# NPKC_alt_PCB.net
KiCad netlist of a schematic drawn in EAGLE
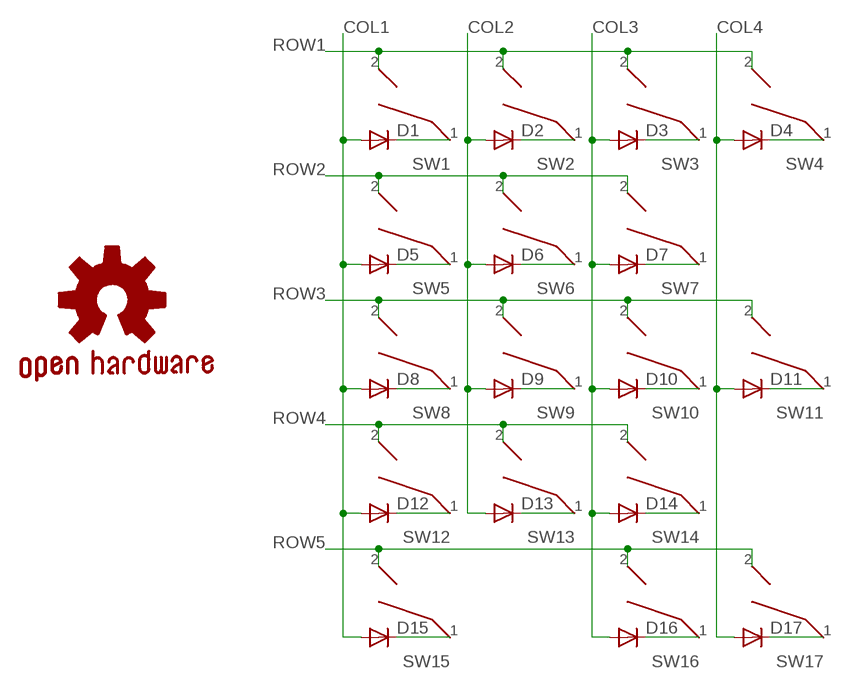
[diagram p0: schematic, sheet 1]
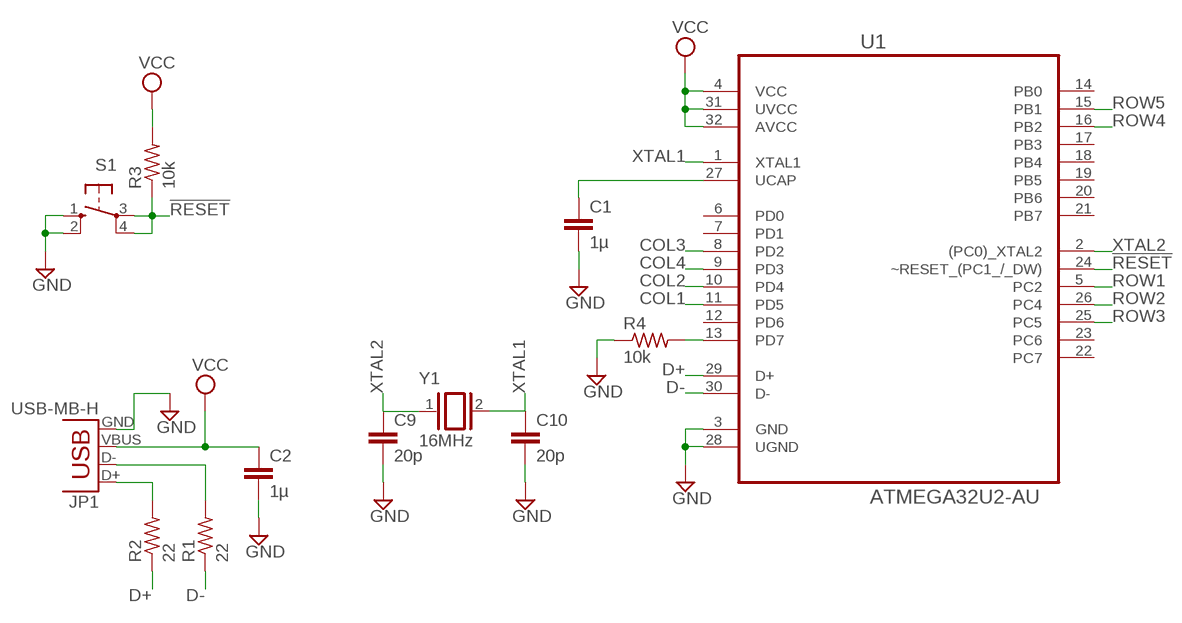
[diagram p1: schematic, sheet 2]

(export (version "E")
  (design (tool "Eeschema 10.0.6"))
  (components
    (comp (ref "D1")
      (value "CGRM4001-G")
      (footprint "eagle-import:SOD-123_MINI-SMA")
      (libsource (lib "eagle-import") (part "CGRM400-G1"))
    )
    (comp (ref "D2")
      (value "CGRM4001-G")
      (footprint "eagle-import:SOD-123_MINI-SMA")
      (libsource (lib "eagle-import") (part "CGRM400-G1"))
    )
    (comp (ref "D3")
      (value "CGRM4001-G")
      (footprint "eagle-import:SOD-123_MINI-SMA")
      (libsource (lib "eagle-import") (part "CGRM400-G1"))
    )
    (comp (ref "D4")
      (value "CGRM4001-G")
      (footprint "eagle-import:SOD-123_MINI-SMA")
      (libsource (lib "eagle-import") (part "CGRM400-G1"))
    )
    (comp (ref "D5")
      (value "CGRM4001-G")
      (footprint "eagle-import:SOD-123_MINI-SMA")
      (libsource (lib "eagle-import") (part "CGRM400-G1"))
    )
    (comp (ref "D6")
      (value "CGRM4001-G")
      (footprint "eagle-import:SOD-123_MINI-SMA")
      (libsource (lib "eagle-import") (part "CGRM400-G1"))
    )
    (comp (ref "D7")
      (value "CGRM4001-G")
      (footprint "eagle-import:SOD-123_MINI-SMA")
      (libsource (lib "eagle-import") (part "CGRM400-G1"))
    )
    (comp (ref "D8")
      (value "CGRM4001-G")
      (footprint "eagle-import:SOD-123_MINI-SMA")
      (libsource (lib "eagle-import") (part "CGRM400-G1"))
    )
    (comp (ref "D9")
      (value "CGRM4001-G")
      (footprint "eagle-import:SOD-123_MINI-SMA")
      (libsource (lib "eagle-import") (part "CGRM400-G1"))
    )
    (comp (ref "D10")
      (value "CGRM4001-G")
      (footprint "eagle-import:SOD-123_MINI-SMA")
      (libsource (lib "eagle-import") (part "CGRM400-G1"))
    )
    (comp (ref "D11")
      (value "CGRM4001-G")
      (footprint "eagle-import:SOD-123_MINI-SMA")
      (libsource (lib "eagle-import") (part "CGRM400-G1"))
    )
    (comp (ref "D12")
      (value "CGRM4001-G")
      (footprint "eagle-import:SOD-123_MINI-SMA")
      (libsource (lib "eagle-import") (part "CGRM400-G1"))
    )
    (comp (ref "D13")
      (value "CGRM4001-G")
      (footprint "eagle-import:SOD-123_MINI-SMA")
      (libsource (lib "eagle-import") (part "CGRM400-G1"))
    )
    (comp (ref "D14")
      (value "CGRM4001-G")
      (footprint "eagle-import:SOD-123_MINI-SMA")
      (libsource (lib "eagle-import") (part "CGRM400-G1"))
    )
    (comp (ref "D15")
      (value "CGRM4001-G")
      (footprint "eagle-import:SOD-123_MINI-SMA")
      (libsource (lib "eagle-import") (part "CGRM400-G1"))
    )
    (comp (ref "D16")
      (value "CGRM4001-G")
      (footprint "eagle-import:SOD-123_MINI-SMA")
      (libsource (lib "eagle-import") (part "CGRM400-G1"))
    )
    (comp (ref "D17")
      (value "CGRM4001-G")
      (footprint "eagle-import:SOD-123_MINI-SMA")
      (libsource (lib "eagle-import") (part "CGRM400-G1"))
    )
    (comp (ref "GOLD_ORB_SM1")
      (value "OSHWLOGO_GOLD_ORB_SM")
      (footprint "eagle-import:OSHW2")
      (libsource (lib "eagle-import") (part "OSHWLOGO_GOLD_ORB_SM"))
    )
    (comp (ref "SW1")
      (value "Num_Lock")
      (footprint "eagle-import:MX1A-XXNW")
      (libsource (lib "eagle-import") (part "CHERRY_MX_WITH_FIXING_PINS"))
    )
    (comp (ref "SW2")
      (value "NP_/")
      (footprint "eagle-import:MX1A-XXNW")
      (libsource (lib "eagle-import") (part "CHERRY_MX_WITH_FIXING_PINS"))
    )
    (comp (ref "SW3")
      (value "NP_*")
      (footprint "eagle-import:MX1A-XXNW")
      (libsource (lib "eagle-import") (part "CHERRY_MX_WITH_FIXING_PINS"))
    )
    (comp (ref "SW4")
      (value "NP_-")
      (footprint "eagle-import:MX1A-XXNW")
      (libsource (lib "eagle-import") (part "CHERRY_MX_WITH_FIXING_PINS"))
    )
    (comp (ref "SW5")
      (value "NP_7")
      (footprint "eagle-import:MX1A-XXNW")
      (libsource (lib "eagle-import") (part "CHERRY_MX_WITH_FIXING_PINS"))
    )
    (comp (ref "SW6")
      (value "NP_8")
      (footprint "eagle-import:MX1A-XXNW")
      (libsource (lib "eagle-import") (part "CHERRY_MX_WITH_FIXING_PINS"))
    )
    (comp (ref "SW7")
      (value "NP_9")
      (footprint "eagle-import:MX1A-XXNW")
      (libsource (lib "eagle-import") (part "CHERRY_MX_WITH_FIXING_PINS"))
    )
    (comp (ref "SW8")
      (value "NP_4")
      (footprint "eagle-import:MX1A-XXNW")
      (libsource (lib "eagle-import") (part "CHERRY_MX_WITH_FIXING_PINS"))
    )
    (comp (ref "SW9")
      (value "NP_5")
      (footprint "eagle-import:MX1A-XXNW")
      (libsource (lib "eagle-import") (part "CHERRY_MX_WITH_FIXING_PINS"))
    )
    (comp (ref "SW10")
      (value "NP_6")
      (footprint "eagle-import:MX1A-XXNW")
      (libsource (lib "eagle-import") (part "CHERRY_MX_WITH_FIXING_PINS"))
    )
    (comp (ref "SW11")
      (value "NP_+")
      (footprint "eagle-import:MX1A-XXNW")
      (libsource (lib "eagle-import") (part "CHERRY_MX_WITH_FIXING_PINS"))
    )
    (comp (ref "SW12")
      (value "NP_1")
      (footprint "eagle-import:MX1A-XXNW")
      (libsource (lib "eagle-import") (part "CHERRY_MX_WITH_FIXING_PINS"))
    )
    (comp (ref "SW13")
      (value "NP_2")
      (footprint "eagle-import:MX1A-XXNW")
      (libsource (lib "eagle-import") (part "CHERRY_MX_WITH_FIXING_PINS"))
    )
    (comp (ref "SW14")
      (value "NP_3")
      (footprint "eagle-import:MX1A-XXNW")
      (libsource (lib "eagle-import") (part "CHERRY_MX_WITH_FIXING_PINS"))
    )
    (comp (ref "SW15")
      (value "NP_0")
      (footprint "eagle-import:MX1A-XXNW")
      (libsource (lib "eagle-import") (part "CHERRY_MX_WITH_FIXING_PINS"))
    )
    (comp (ref "SW16")
      (value "NP_.")
      (footprint "eagle-import:MX1A-XXNW")
      (libsource (lib "eagle-import") (part "CHERRY_MX_WITH_FIXING_PINS"))
    )
    (comp (ref "SW17")
      (value "NP_Enter")
      (footprint "eagle-import:MX1A-XXNW")
      (libsource (lib "eagle-import") (part "CHERRY_MX_WITH_FIXING_PINS"))
    )
    (comp (ref "C1")
      (value "1µ")
      (footprint "eagle-import:C0805K")
      (libsource (lib "eagle-import") (part "C-EUC0805K"))
    )
    (comp (ref "C2")
      (value "1µ")
      (footprint "eagle-import:C0805")
      (libsource (lib "eagle-import") (part "C-EUC0805"))
    )
    (comp (ref "C9")
      (value "20p")
      (footprint "eagle-import:C0805K")
      (libsource (lib "eagle-import") (part "C-EUC0805K"))
    )
    (comp (ref "C10")
      (value "20p")
      (footprint "eagle-import:C0805K")
      (libsource (lib "eagle-import") (part "C-EUC0805K"))
    )
    (comp (ref "JP1")
      (value "USB-MB-H")
      (footprint "eagle-import:USB-MB-H")
      (libsource (lib "eagle-import") (part "USB-MB-H"))
    )
    (comp (ref "R1")
      (value "22")
      (footprint "eagle-import:R0805")
      (libsource (lib "eagle-import") (part "R-US_R0805"))
    )
    (comp (ref "R2")
      (value "22")
      (footprint "eagle-import:R0805")
      (libsource (lib "eagle-import") (part "R-US_R0805"))
    )
    (comp (ref "R3")
      (value "10k")
      (footprint "eagle-import:R0805")
      (libsource (lib "eagle-import") (part "R-US_R0805"))
    )
    (comp (ref "R4")
      (value "10k")
      (footprint "eagle-import:R0805")
      (libsource (lib "eagle-import") (part "R-US_R0805"))
    )
    (comp (ref "S1")
      (value "10-XX")
      (footprint "eagle-import:B3F-10XX")
      (fields (field (name "MPN") "B3F-1000"))
      (libsource (lib "eagle-import") (part "10-XX"))
    )
    (comp (ref "U1")
      (value "ATMEGA32U2-AU")
      (footprint "eagle-import:QFP80P900X900X120-32N")
      (libsource (lib "eagle-import") (part "ATMEGA32U2-AU"))
    )
    (comp (ref "Y1")
      (value "16MHz")
      (footprint "eagle-import:QS")
      (libsource (lib "eagle-import") (part "XTAL/S"))
    )
  )
  (nets
    (net (code "1") (name "COL1") (class "Default")
      (node (ref "D1") (pin "A") (pinfunction "A_A") (pintype "passive"))
      (node (ref "D12") (pin "A") (pinfunction "A_A") (pintype "passive"))
      (node (ref "D15") (pin "A") (pinfunction "A_A") (pintype "passive"))
      (node (ref "D5") (pin "A") (pinfunction "A_A") (pintype "passive"))
      (node (ref "D8") (pin "A") (pinfunction "A_A") (pintype "passive"))
      (node (ref "U1") (pin "11") (pinfunction "PD5_11") (pintype "bidirectional"))
    )
    (net (code "2") (name "COL2") (class "Default")
      (node (ref "D13") (pin "A") (pinfunction "A_A") (pintype "passive"))
      (node (ref "D2") (pin "A") (pinfunction "A_A") (pintype "passive"))
      (node (ref "D6") (pin "A") (pinfunction "A_A") (pintype "passive"))
      (node (ref "D9") (pin "A") (pinfunction "A_A") (pintype "passive"))
      (node (ref "U1") (pin "10") (pinfunction "PD4_10") (pintype "bidirectional"))
    )
    (net (code "3") (name "COL3") (class "Default")
      (node (ref "D10") (pin "A") (pinfunction "A_A") (pintype "passive"))
      (node (ref "D14") (pin "A") (pinfunction "A_A") (pintype "passive"))
      (node (ref "D16") (pin "A") (pinfunction "A_A") (pintype "passive"))
      (node (ref "D3") (pin "A") (pinfunction "A_A") (pintype "passive"))
      (node (ref "D7") (pin "A") (pinfunction "A_A") (pintype "passive"))
      (node (ref "U1") (pin "8") (pinfunction "PD2_8") (pintype "bidirectional"))
    )
    (net (code "4") (name "COL4") (class "Default")
      (node (ref "D11") (pin "A") (pinfunction "A_A") (pintype "passive"))
      (node (ref "D17") (pin "A") (pinfunction "A_A") (pintype "passive"))
      (node (ref "D4") (pin "A") (pinfunction "A_A") (pintype "passive"))
      (node (ref "U1") (pin "9") (pinfunction "PD3_9") (pintype "bidirectional"))
    )
    (net (code "5") (name "D+") (class "Default")
      (node (ref "R2") (pin "1") (pinfunction "1_1") (pintype "passive"))
      (node (ref "U1") (pin "29") (pinfunction "D+_29") (pintype "bidirectional"))
    )
    (net (code "6") (name "D-") (class "Default")
      (node (ref "R1") (pin "1") (pinfunction "1_1") (pintype "passive"))
      (node (ref "U1") (pin "30") (pinfunction "D-_30") (pintype "bidirectional"))
    )
    (net (code "7") (name "GND") (class "Default")
      (node (ref "C1") (pin "2") (pinfunction "2_2") (pintype "passive"))
      (node (ref "C10") (pin "2") (pinfunction "2_2") (pintype "passive"))
      (node (ref "C2") (pin "2") (pinfunction "2_2") (pintype "passive"))
      (node (ref "C9") (pin "2") (pinfunction "2_2") (pintype "passive"))
      (node (ref "JP1") (pin "GND") (pinfunction "GND_GND") (pintype "bidirectional"))
      (node (ref "R4") (pin "1") (pinfunction "1_1") (pintype "passive"))
      (node (ref "S1") (pin "1") (pinfunction "S_1") (pintype "passive"))
      (node (ref "S1") (pin "2") (pinfunction "S1_2") (pintype "passive"))
      (node (ref "U1") (pin "28") (pinfunction "UGND_28") (pintype "passive"))
      (node (ref "U1") (pin "3") (pinfunction "GND_3") (pintype "passive"))
    )
    (net (code "8") (name "Net-(D1-PadC)") (class "Default")
      (node (ref "D1") (pin "C") (pinfunction "C_C") (pintype "passive"))
      (node (ref "SW1") (pin "1") (pinfunction "1_1") (pintype "passive"))
    )
    (net (code "9") (name "Net-(D2-PadC)") (class "Default")
      (node (ref "D2") (pin "C") (pinfunction "C_C") (pintype "passive"))
      (node (ref "SW2") (pin "1") (pinfunction "1_1") (pintype "passive"))
    )
    (net (code "10") (name "Net-(D3-PadC)") (class "Default")
      (node (ref "D3") (pin "C") (pinfunction "C_C") (pintype "passive"))
      (node (ref "SW3") (pin "1") (pinfunction "1_1") (pintype "passive"))
    )
    (net (code "11") (name "Net-(D4-PadC)") (class "Default")
      (node (ref "D4") (pin "C") (pinfunction "C_C") (pintype "passive"))
      (node (ref "SW4") (pin "1") (pinfunction "1_1") (pintype "passive"))
    )
    (net (code "12") (name "Net-(D5-PadC)") (class "Default")
      (node (ref "D5") (pin "C") (pinfunction "C_C") (pintype "passive"))
      (node (ref "SW5") (pin "1") (pinfunction "1_1") (pintype "passive"))
    )
    (net (code "13") (name "Net-(D6-PadC)") (class "Default")
      (node (ref "D6") (pin "C") (pinfunction "C_C") (pintype "passive"))
      (node (ref "SW6") (pin "1") (pinfunction "1_1") (pintype "passive"))
    )
    (net (code "14") (name "Net-(D7-PadC)") (class "Default")
      (node (ref "D7") (pin "C") (pinfunction "C_C") (pintype "passive"))
      (node (ref "SW7") (pin "1") (pinfunction "1_1") (pintype "passive"))
    )
    (net (code "15") (name "Net-(D8-PadC)") (class "Default")
      (node (ref "D8") (pin "C") (pinfunction "C_C") (pintype "passive"))
      (node (ref "SW8") (pin "1") (pinfunction "1_1") (pintype "passive"))
    )
    (net (code "16") (name "Net-(D9-PadC)") (class "Default")
      (node (ref "D9") (pin "C") (pinfunction "C_C") (pintype "passive"))
      (node (ref "SW9") (pin "1") (pinfunction "1_1") (pintype "passive"))
    )
    (net (code "17") (name "Net-(D10-PadC)") (class "Default")
      (node (ref "D10") (pin "C") (pinfunction "C_C") (pintype "passive"))
      (node (ref "SW10") (pin "1") (pinfunction "1_1") (pintype "passive"))
    )
    (net (code "18") (name "Net-(D11-PadC)") (class "Default")
      (node (ref "D11") (pin "C") (pinfunction "C_C") (pintype "passive"))
      (node (ref "SW11") (pin "1") (pinfunction "1_1") (pintype "passive"))
    )
    (net (code "19") (name "Net-(D12-PadC)") (class "Default")
      (node (ref "D12") (pin "C") (pinfunction "C_C") (pintype "passive"))
      (node (ref "SW12") (pin "1") (pinfunction "1_1") (pintype "passive"))
    )
    (net (code "20") (name "Net-(D13-PadC)") (class "Default")
      (node (ref "D13") (pin "C") (pinfunction "C_C") (pintype "passive"))
      (node (ref "SW13") (pin "1") (pinfunction "1_1") (pintype "passive"))
    )
    (net (code "21") (name "Net-(D14-PadC)") (class "Default")
      (node (ref "D14") (pin "C") (pinfunction "C_C") (pintype "passive"))
      (node (ref "SW14") (pin "1") (pinfunction "1_1") (pintype "passive"))
    )
    (net (code "22") (name "Net-(D15-PadC)") (class "Default")
      (node (ref "D15") (pin "C") (pinfunction "C_C") (pintype "passive"))
      (node (ref "SW15") (pin "1") (pinfunction "1_1") (pintype "passive"))
    )
    (net (code "23") (name "Net-(D16-PadC)") (class "Default")
      (node (ref "D16") (pin "C") (pinfunction "C_C") (pintype "passive"))
      (node (ref "SW16") (pin "1") (pinfunction "1_1") (pintype "passive"))
    )
    (net (code "24") (name "Net-(D17-PadC)") (class "Default")
      (node (ref "D17") (pin "C") (pinfunction "C_C") (pintype "passive"))
      (node (ref "SW17") (pin "1") (pinfunction "1_1") (pintype "passive"))
    )
    (net (code "25") (name "Net-(JP1-PadD+)") (class "Default")
      (node (ref "JP1") (pin "D+") (pinfunction "D+_D+") (pintype "bidirectional"))
      (node (ref "R2") (pin "2") (pinfunction "2_2") (pintype "passive"))
    )
    (net (code "26") (name "Net-(JP1-PadD-)") (class "Default")
      (node (ref "JP1") (pin "D-") (pinfunction "D-_D-") (pintype "bidirectional"))
      (node (ref "R1") (pin "2") (pinfunction "2_2") (pintype "passive"))
    )
    (net (code "27") (name "Net-(U1-PD7)") (class "Default")
      (node (ref "R4") (pin "2") (pinfunction "2_2") (pintype "passive"))
      (node (ref "U1") (pin "13") (pinfunction "PD7_13") (pintype "bidirectional"))
    )
    (net (code "28") (name "Net-(U1-UCAP)") (class "Default")
      (node (ref "C1") (pin "1") (pinfunction "1_1") (pintype "passive"))
      (node (ref "U1") (pin "27") (pinfunction "UCAP_27") (pintype "power_in"))
    )
    (net (code "29") (name "ROW1") (class "Default")
      (node (ref "SW1") (pin "2") (pinfunction "2_2") (pintype "passive"))
      (node (ref "SW2") (pin "2") (pinfunction "2_2") (pintype "passive"))
      (node (ref "SW3") (pin "2") (pinfunction "2_2") (pintype "passive"))
      (node (ref "SW4") (pin "2") (pinfunction "2_2") (pintype "passive"))
      (node (ref "U1") (pin "5") (pinfunction "PC2_5") (pintype "bidirectional"))
    )
    (net (code "30") (name "ROW2") (class "Default")
      (node (ref "SW5") (pin "2") (pinfunction "2_2") (pintype "passive"))
      (node (ref "SW6") (pin "2") (pinfunction "2_2") (pintype "passive"))
      (node (ref "SW7") (pin "2") (pinfunction "2_2") (pintype "passive"))
      (node (ref "U1") (pin "26") (pinfunction "PC4_26") (pintype "bidirectional"))
    )
    (net (code "31") (name "ROW3") (class "Default")
      (node (ref "SW10") (pin "2") (pinfunction "2_2") (pintype "passive"))
      (node (ref "SW11") (pin "2") (pinfunction "2_2") (pintype "passive"))
      (node (ref "SW8") (pin "2") (pinfunction "2_2") (pintype "passive"))
      (node (ref "SW9") (pin "2") (pinfunction "2_2") (pintype "passive"))
      (node (ref "U1") (pin "25") (pinfunction "PC5_25") (pintype "bidirectional"))
    )
    (net (code "32") (name "ROW4") (class "Default")
      (node (ref "SW12") (pin "2") (pinfunction "2_2") (pintype "passive"))
      (node (ref "SW13") (pin "2") (pinfunction "2_2") (pintype "passive"))
      (node (ref "SW14") (pin "2") (pinfunction "2_2") (pintype "passive"))
      (node (ref "U1") (pin "16") (pinfunction "PB2_16") (pintype "bidirectional"))
    )
    (net (code "33") (name "ROW5") (class "Default")
      (node (ref "SW15") (pin "2") (pinfunction "2_2") (pintype "passive"))
      (node (ref "SW16") (pin "2") (pinfunction "2_2") (pintype "passive"))
      (node (ref "SW17") (pin "2") (pinfunction "2_2") (pintype "passive"))
      (node (ref "U1") (pin "15") (pinfunction "PB1_15") (pintype "bidirectional"))
    )
    (net (code "34") (name "VCC") (class "Default")
      (node (ref "C2") (pin "1") (pinfunction "1_1") (pintype "passive"))
      (node (ref "JP1") (pin "VBUS") (pinfunction "VBUS_VBUS") (pintype "bidirectional"))
      (node (ref "R3") (pin "2") (pinfunction "2_2") (pintype "passive"))
      (node (ref "U1") (pin "31") (pinfunction "UVCC_31") (pintype "power_in"))
      (node (ref "U1") (pin "32") (pinfunction "AVCC_32") (pintype "power_in"))
      (node (ref "U1") (pin "4") (pinfunction "VCC_4") (pintype "power_in"))
    )
    (net (code "35") (name "XTAL1") (class "Default")
      (node (ref "C10") (pin "1") (pinfunction "1_1") (pintype "passive"))
      (node (ref "U1") (pin "1") (pinfunction "XTAL1_1") (pintype "input"))
      (node (ref "Y1") (pin "2") (pinfunction "2_2") (pintype "passive"))
    )
    (net (code "36") (name "XTAL2") (class "Default")
      (node (ref "C9") (pin "1") (pinfunction "1_1") (pintype "passive"))
      (node (ref "U1") (pin "2") (pinfunction "(PC0)_XTAL2_2") (pintype "bidirectional"))
      (node (ref "Y1") (pin "1") (pinfunction "1_1") (pintype "passive"))
    )
    (net (code "37") (name "unconnected-(U1-PB0-Pad14)") (class "Default")
      (node (ref "U1") (pin "14") (pinfunction "PB0_14") (pintype "bidirectional"))
    )
    (net (code "38") (name "unconnected-(U1-PB3-Pad17)") (class "Default")
      (node (ref "U1") (pin "17") (pinfunction "PB3_17") (pintype "bidirectional"))
    )
    (net (code "39") (name "unconnected-(U1-PB4-Pad18)") (class "Default")
      (node (ref "U1") (pin "18") (pinfunction "PB4_18") (pintype "bidirectional"))
    )
    (net (code "40") (name "unconnected-(U1-PB5-Pad19)") (class "Default")
      (node (ref "U1") (pin "19") (pinfunction "PB5_19") (pintype "bidirectional"))
    )
    (net (code "41") (name "unconnected-(U1-PB6-Pad20)") (class "Default")
      (node (ref "U1") (pin "20") (pinfunction "PB6_20") (pintype "bidirectional"))
    )
    (net (code "42") (name "unconnected-(U1-PB7-Pad21)") (class "Default")
      (node (ref "U1") (pin "21") (pinfunction "PB7_21") (pintype "bidirectional"))
    )
    (net (code "43") (name "unconnected-(U1-PC6-Pad23)") (class "Default")
      (node (ref "U1") (pin "23") (pinfunction "PC6_23") (pintype "bidirectional"))
    )
    (net (code "44") (name "unconnected-(U1-PC7-Pad22)") (class "Default")
      (node (ref "U1") (pin "22") (pinfunction "PC7_22") (pintype "bidirectional"))
    )
    (net (code "45") (name "unconnected-(U1-PD0-Pad6)") (class "Default")
      (node (ref "U1") (pin "6") (pinfunction "PD0_6") (pintype "bidirectional"))
    )
    (net (code "46") (name "unconnected-(U1-PD1-Pad7)") (class "Default")
      (node (ref "U1") (pin "7") (pinfunction "PD1_7") (pintype "bidirectional"))
    )
    (net (code "47") (name "unconnected-(U1-PD6-Pad12)") (class "Default")
      (node (ref "U1") (pin "12") (pinfunction "PD6_12") (pintype "bidirectional"))
    )
    (net (code "48") (name "~{RESET}") (class "Default")
      (node (ref "R3") (pin "1") (pinfunction "1_1") (pintype "passive"))
      (node (ref "S1") (pin "3") (pinfunction "P_3") (pintype "passive"))
      (node (ref "S1") (pin "4") (pinfunction "P1_4") (pintype "passive"))
      (node (ref "U1") (pin "24") (pinfunction "~{RESET_(PC1_/_DW})_24") (pintype "bidirectional"))
    )
  )
)
